# AA_version.net
KiCad netlist of a schematic drawn in EAGLE
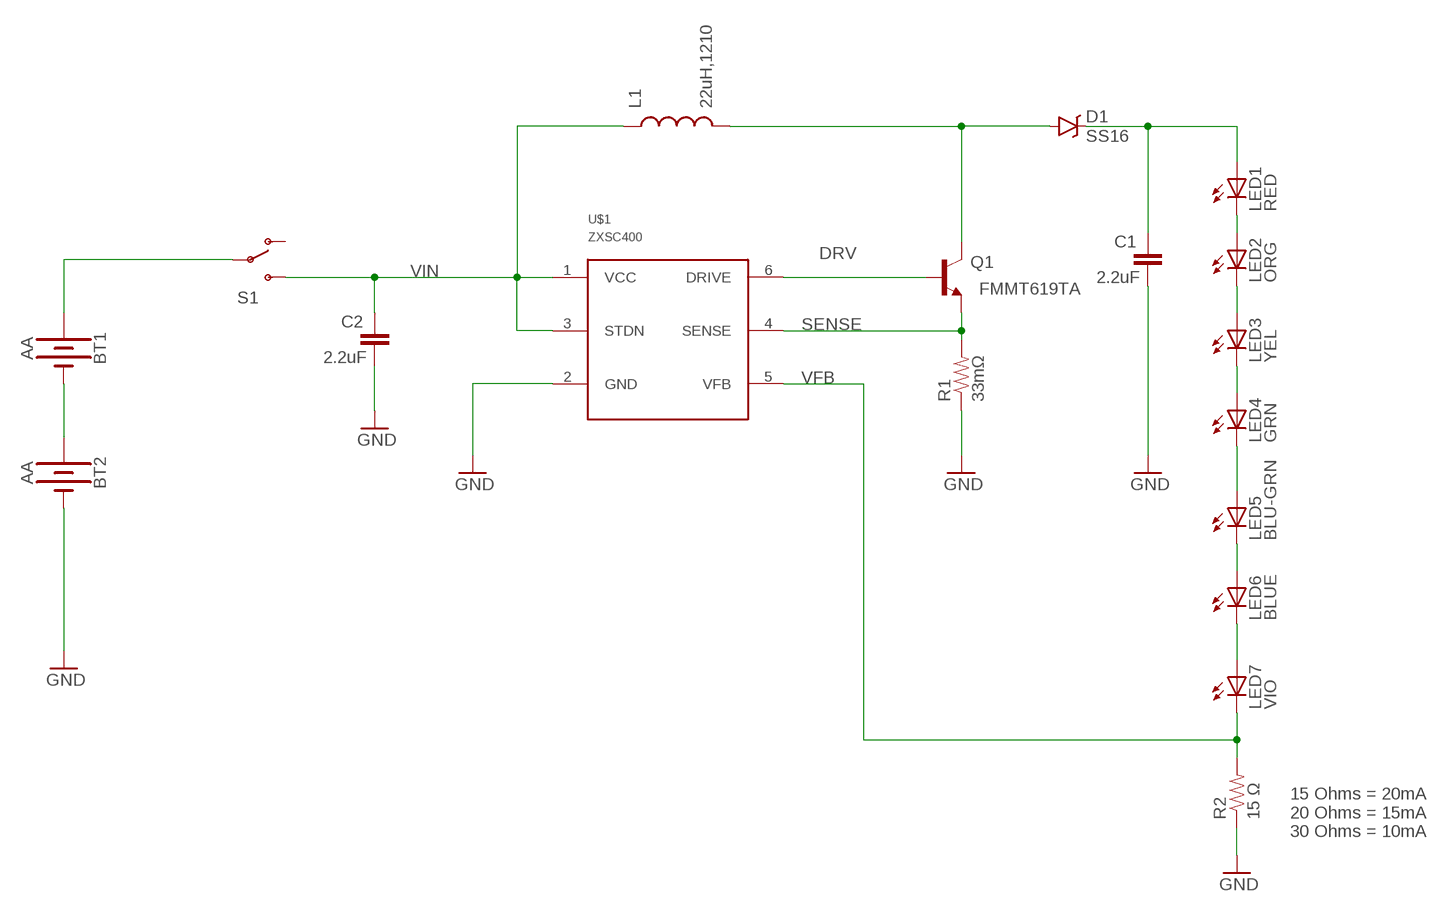
[diagram p0: schematic, sheet 1]

(export (version "E")
  (design (tool "Eeschema 10.0.6"))
  (components
    (comp (ref "BT1")
      (value "AA")
      (footprint "eagle-import:BATTERY-AA")
      (libsource (lib "eagle-import") (part "BATTERY-AA"))
    )
    (comp (ref "BT2")
      (value "AA")
      (footprint "eagle-import:BATTERY-AA")
      (libsource (lib "eagle-import") (part "BATTERY-AA"))
    )
    (comp (ref "C1")
      (value "2.2uF")
      (footprint "eagle-import:1206")
      (libsource (lib "eagle-import") (part "CAP1206"))
    )
    (comp (ref "C2")
      (value "2.2uF")
      (footprint "eagle-import:1206")
      (libsource (lib "eagle-import") (part "CAP1206"))
    )
    (comp (ref "D1")
      (value "SS16")
      (footprint "eagle-import:SMA-DIODE")
      (libsource (lib "eagle-import") (part "DIODE-SCHOTTKY-B340A"))
    )
    (comp (ref "L1")
      (value "22uH,1210")
      (footprint "eagle-import:1210")
      (libsource (lib "eagle-import") (part "INDUCTOR1210"))
    )
    (comp (ref "LED1")
      (value "RED")
      (footprint "eagle-import:P-LCC-2")
      (libsource (lib "eagle-import") (part "LEDP-LCC-2"))
    )
    (comp (ref "LED2")
      (value "ORG")
      (footprint "eagle-import:P-LCC-2")
      (libsource (lib "eagle-import") (part "LEDP-LCC-2"))
    )
    (comp (ref "LED3")
      (value "YEL")
      (footprint "eagle-import:P-LCC-2")
      (libsource (lib "eagle-import") (part "LEDP-LCC-2"))
    )
    (comp (ref "LED4")
      (value "GRN")
      (footprint "eagle-import:P-LCC-2")
      (libsource (lib "eagle-import") (part "LEDP-LCC-2"))
    )
    (comp (ref "LED5")
      (value "BLU-GRN")
      (footprint "eagle-import:P-LCC-2")
      (libsource (lib "eagle-import") (part "LEDP-LCC-2"))
    )
    (comp (ref "LED6")
      (value "BLUE")
      (footprint "eagle-import:P-LCC-2")
      (libsource (lib "eagle-import") (part "LEDP-LCC-2"))
    )
    (comp (ref "LED7")
      (value "VIO")
      (footprint "eagle-import:P-LCC-2")
      (libsource (lib "eagle-import") (part "LEDP-LCC-2"))
    )
    (comp (ref "Q1")
      (value "FMMT619TA")
      (footprint "eagle-import:SOT23-3")
      (libsource (lib "eagle-import") (part "TRANSISTOR_NPNSOT23-3"))
    )
    (comp (ref "R1")
      (value "33mΩ")
      (footprint "eagle-import:1206")
      (libsource (lib "eagle-import") (part "RESISTOR1206"))
    )
    (comp (ref "R2")
      (value "15 Ω")
      (footprint "eagle-import:1206")
      (libsource (lib "eagle-import") (part "RESISTOR1206"))
    )
    (comp (ref "S1")
      (value "SWITCH-SPDTPTH_LOCK")
      (footprint "eagle-import:SWITCH-SPDT_LOCK.007S")
      (libsource (lib "eagle-import") (part "SWITCH-SPDTPTH_LOCK"))
    )
    (comp (ref "U$1")
      (value "ZXSC400")
      (footprint "eagle-import:SOT23-6")
      (libsource (lib "eagle-import") (part "ZXSC400"))
    )
  )
  (nets
    (net (code "1") (name "/DRV") (class "Default")
      (node (ref "Q1") (pin "1") (pinfunction "B_1") (pintype "passive"))
      (node (ref "U$1") (pin "6") (pinfunction "DRIVE_6") (pintype "bidirectional"))
    )
    (net (code "2") (name "/SENSE") (class "Default")
      (node (ref "Q1") (pin "2") (pinfunction "E_2") (pintype "passive"))
      (node (ref "R1") (pin "2") (pinfunction "2_2") (pintype "passive"))
      (node (ref "U$1") (pin "4") (pinfunction "SENSE_4") (pintype "bidirectional"))
    )
    (net (code "3") (name "/VFB") (class "Default")
      (node (ref "LED7") (pin "C") (pinfunction "C_C") (pintype "passive"))
      (node (ref "R2") (pin "2") (pinfunction "2_2") (pintype "passive"))
      (node (ref "U$1") (pin "5") (pinfunction "VFB_5") (pintype "bidirectional"))
    )
    (net (code "4") (name "/VIN") (class "Default")
      (node (ref "C2") (pin "2") (pinfunction "2_2") (pintype "passive"))
      (node (ref "L1") (pin "1") (pinfunction "1_1") (pintype "passive"))
      (node (ref "S1") (pin "3") (pinfunction "S_3") (pintype "passive"))
      (node (ref "U$1") (pin "1") (pinfunction "VCC_1") (pintype "bidirectional"))
      (node (ref "U$1") (pin "3") (pinfunction "STDN_3") (pintype "bidirectional"))
    )
    (net (code "5") (name "GND") (class "Default")
      (node (ref "BT2") (pin "GND@1") (pinfunction "-_GND@1") (pintype "power_in"))
      (node (ref "C1") (pin "1") (pinfunction "1_1") (pintype "passive"))
      (node (ref "C2") (pin "1") (pinfunction "1_1") (pintype "passive"))
      (node (ref "R1") (pin "1") (pinfunction "1_1") (pintype "passive"))
      (node (ref "R2") (pin "1") (pinfunction "1_1") (pintype "passive"))
      (node (ref "U$1") (pin "2") (pinfunction "GND_2") (pintype "bidirectional"))
    )
    (net (code "6") (name "Net-(BT1-+)") (class "Default")
      (node (ref "BT1") (pin "PWR@1") (pinfunction "+_PWR@1") (pintype "power_in"))
      (node (ref "S1") (pin "2") (pinfunction "P_2") (pintype "passive"))
    )
    (net (code "7") (name "Net-(BT1--)") (class "Default")
      (node (ref "BT1") (pin "GND@1") (pinfunction "-_GND@1") (pintype "power_in"))
      (node (ref "BT2") (pin "PWR@1") (pinfunction "+_PWR@1") (pintype "power_in"))
    )
    (net (code "8") (name "Net-(C1-Pad2)") (class "Default")
      (node (ref "C1") (pin "2") (pinfunction "2_2") (pintype "passive"))
      (node (ref "D1") (pin "C") (pinfunction "C_C") (pintype "passive"))
      (node (ref "LED1") (pin "A") (pinfunction "A_A") (pintype "passive"))
    )
    (net (code "9") (name "Net-(LED1-PadC)") (class "Default")
      (node (ref "LED1") (pin "C") (pinfunction "C_C") (pintype "passive"))
      (node (ref "LED2") (pin "A") (pinfunction "A_A") (pintype "passive"))
    )
    (net (code "10") (name "Net-(LED2-PadC)") (class "Default")
      (node (ref "LED2") (pin "C") (pinfunction "C_C") (pintype "passive"))
      (node (ref "LED3") (pin "A") (pinfunction "A_A") (pintype "passive"))
    )
    (net (code "11") (name "Net-(LED3-PadC)") (class "Default")
      (node (ref "LED3") (pin "C") (pinfunction "C_C") (pintype "passive"))
      (node (ref "LED4") (pin "A") (pinfunction "A_A") (pintype "passive"))
    )
    (net (code "12") (name "Net-(LED4-PadC)") (class "Default")
      (node (ref "LED4") (pin "C") (pinfunction "C_C") (pintype "passive"))
      (node (ref "LED5") (pin "A") (pinfunction "A_A") (pintype "passive"))
    )
    (net (code "13") (name "Net-(LED5-PadC)") (class "Default")
      (node (ref "LED5") (pin "C") (pinfunction "C_C") (pintype "passive"))
      (node (ref "LED6") (pin "A") (pinfunction "A_A") (pintype "passive"))
    )
    (net (code "14") (name "Net-(LED6-PadC)") (class "Default")
      (node (ref "LED6") (pin "C") (pinfunction "C_C") (pintype "passive"))
      (node (ref "LED7") (pin "A") (pinfunction "A_A") (pintype "passive"))
    )
    (net (code "15") (name "Net-(Q1-C)") (class "Default")
      (node (ref "D1") (pin "A") (pinfunction "A_A") (pintype "passive"))
      (node (ref "L1") (pin "2") (pinfunction "2_2") (pintype "passive"))
      (node (ref "Q1") (pin "3") (pinfunction "C_3") (pintype "passive"))
    )
    (net (code "16") (name "unconnected-(S1-O-Pad1)") (class "Default")
      (node (ref "S1") (pin "1") (pinfunction "O_1") (pintype "passive"))
    )
  )
)
